# DorMouse.net
KiCad netlist of a schematic drawn in EAGLE
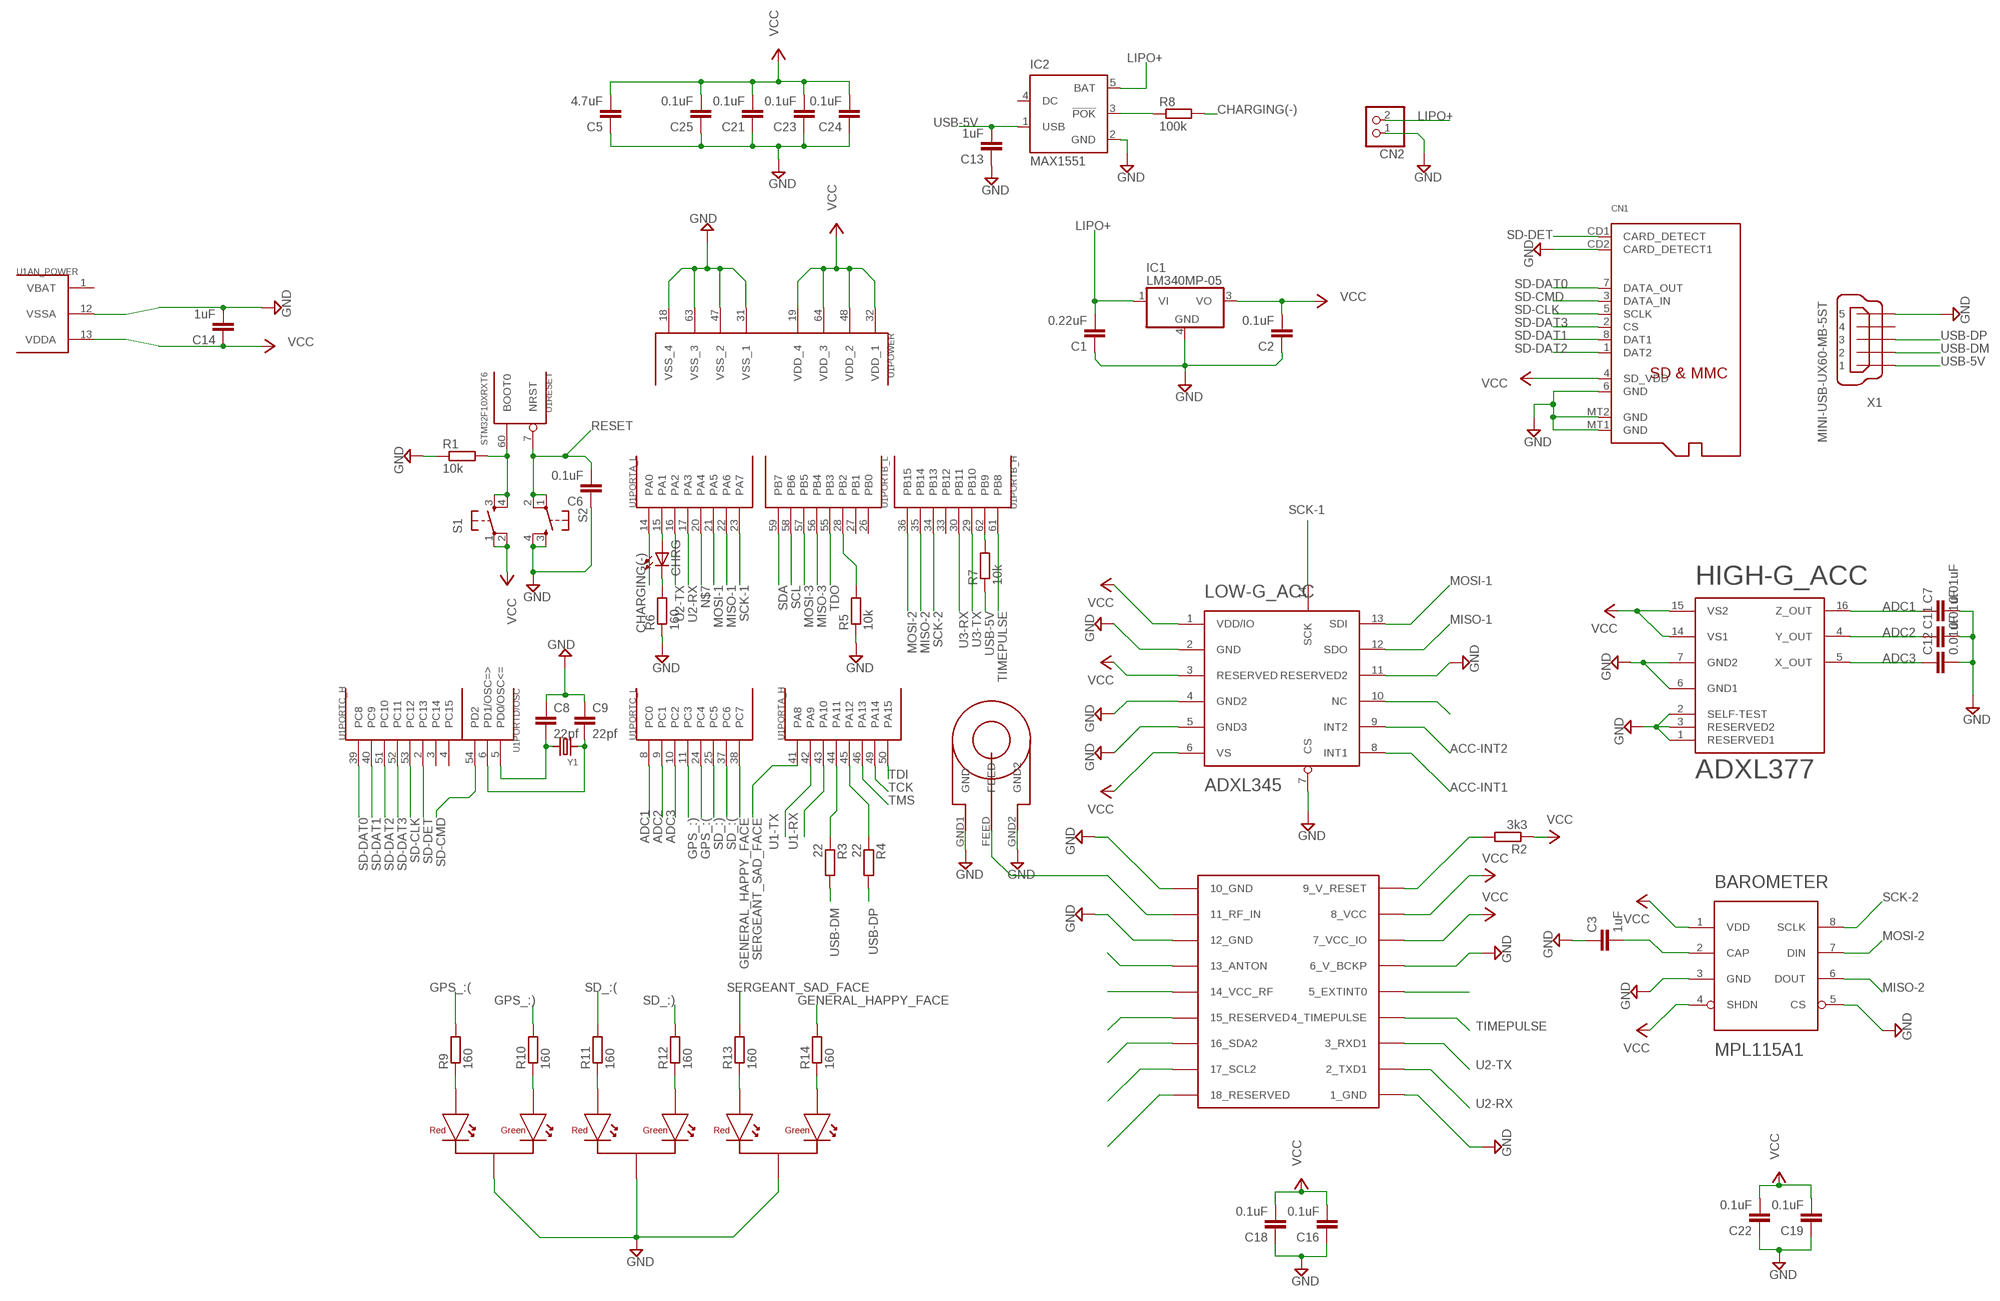
[diagram p0: schematic, sheet 1, part 1 of 2]
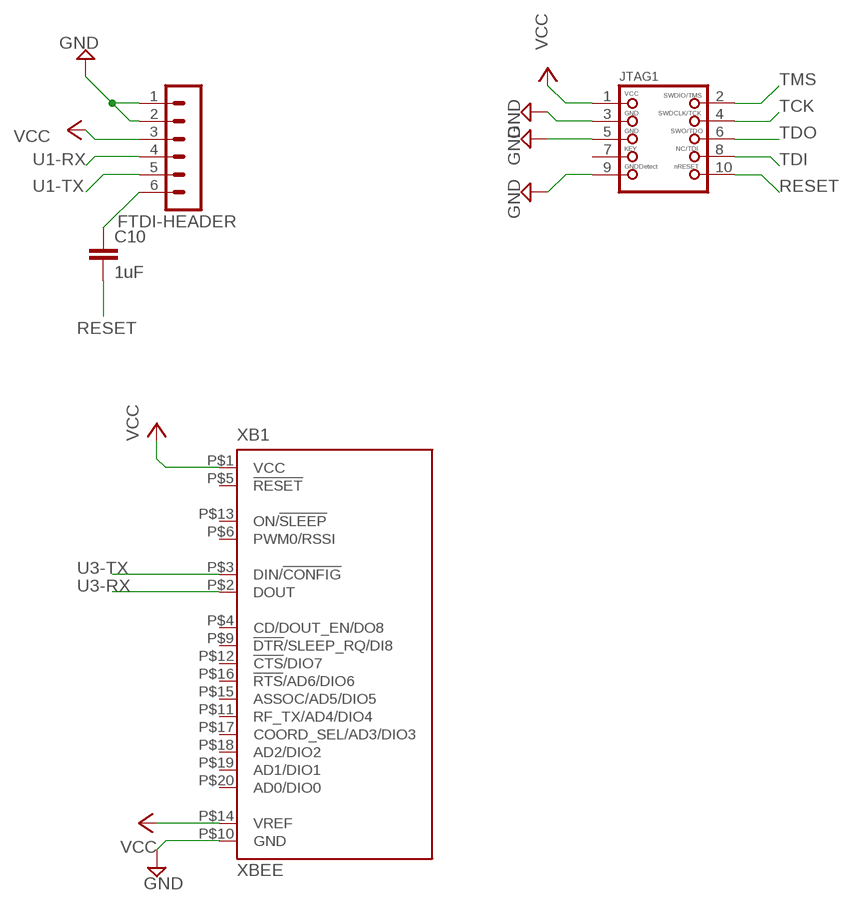
[diagram p1: schematic, sheet 1, part 2 of 2]

(export (version "E")
  (design (tool "Eeschema 10.0.6"))
  (components
    (comp (ref "BAROMETER")
      (value "MPL115A1")
      (footprint "eagle-import:LGA-8")
      (libsource (lib "eagle-import") (part "MPL115A1"))
    )
    (comp (ref "C1")
      (value "0.22uF")
      (footprint "eagle-import:C0402")
      (libsource (lib "eagle-import") (part "C-EUC0402"))
    )
    (comp (ref "C2")
      (value "0.1uF")
      (footprint "eagle-import:C0402")
      (libsource (lib "eagle-import") (part "C-EUC0402"))
    )
    (comp (ref "C3")
      (value "1uF")
      (footprint "eagle-import:C0402")
      (libsource (lib "eagle-import") (part "C-EUC0402"))
    )
    (comp (ref "C5")
      (value "4.7uF")
      (footprint "eagle-import:C0402")
      (libsource (lib "eagle-import") (part "C-EUC0402"))
    )
    (comp (ref "C6")
      (value "0.1uF")
      (footprint "eagle-import:C0402")
      (libsource (lib "eagle-import") (part "C-EUC0402"))
    )
    (comp (ref "C7")
      (value "0.01uF")
      (footprint "eagle-import:C0402")
      (libsource (lib "eagle-import") (part "C-EUC0402"))
    )
    (comp (ref "C8")
      (value "22pf")
      (footprint "eagle-import:C0402")
      (libsource (lib "eagle-import") (part "C-EUC0402"))
    )
    (comp (ref "C9")
      (value "22pf")
      (footprint "eagle-import:C0402")
      (libsource (lib "eagle-import") (part "C-EUC0402"))
    )
    (comp (ref "C10")
      (value "1uF")
      (footprint "eagle-import:C0402")
      (libsource (lib "eagle-import") (part "C-EUC0402"))
    )
    (comp (ref "C11")
      (value "0.01uF")
      (footprint "eagle-import:C0402")
      (libsource (lib "eagle-import") (part "C-EUC0402"))
    )
    (comp (ref "C12")
      (value "0.01uF")
      (footprint "eagle-import:C0402")
      (libsource (lib "eagle-import") (part "C-EUC0402"))
    )
    (comp (ref "C13")
      (value "1uF")
      (footprint "eagle-import:C0402")
      (libsource (lib "eagle-import") (part "C-EUC0402"))
    )
    (comp (ref "C14")
      (value "1uF")
      (footprint "eagle-import:C0402")
      (libsource (lib "eagle-import") (part "C-EUC0402"))
    )
    (comp (ref "C16")
      (value "0.1uF")
      (footprint "eagle-import:C0402")
      (libsource (lib "eagle-import") (part "C-EUC0402"))
    )
    (comp (ref "C18")
      (value "0.1uF")
      (footprint "eagle-import:C0402")
      (libsource (lib "eagle-import") (part "C-EUC0402"))
    )
    (comp (ref "C19")
      (value "0.1uF")
      (footprint "eagle-import:C0402")
      (libsource (lib "eagle-import") (part "C-EUC0402"))
    )
    (comp (ref "C21")
      (value "0.1uF")
      (footprint "eagle-import:C0402")
      (libsource (lib "eagle-import") (part "C-EUC0402"))
    )
    (comp (ref "C22")
      (value "0.1uF")
      (footprint "eagle-import:C0402")
      (libsource (lib "eagle-import") (part "C-EUC0402"))
    )
    (comp (ref "C23")
      (value "0.1uF")
      (footprint "eagle-import:C0402")
      (libsource (lib "eagle-import") (part "C-EUC0402"))
    )
    (comp (ref "C24")
      (value "0.1uF")
      (footprint "eagle-import:C0402")
      (libsource (lib "eagle-import") (part "C-EUC0402"))
    )
    (comp (ref "C25")
      (value "0.1uF")
      (footprint "eagle-import:C0402")
      (libsource (lib "eagle-import") (part "C-EUC0402"))
    )
    (comp (ref "CHRG")
      (value "LEDCHIPLED_0603")
      (footprint "eagle-import:CHIPLED_0603")
      (libsource (lib "eagle-import") (part "LEDCHIPLED_0603"))
    )
    (comp (ref "CN1")
      (value "MICROSD")
      (footprint "eagle-import:MICROSD")
      (libsource (lib "eagle-import") (part "MICROSD"))
    )
    (comp (ref "CN2")
      (value "JST_2PINSH2")
      (footprint "eagle-import:JSTSH2")
      (libsource (lib "eagle-import") (part "JST_2PINSH2"))
    )
    (comp (ref "FTDI-HEADER")
      (value "MA06-1")
      (footprint "eagle-import:MA06-1")
      (libsource (lib "eagle-import") (part "MA06-1"))
    )
    (comp (ref "GENERAL")
      (value "RED-GREEN_LED")
      (footprint "eagle-import:SOT23")
      (libsource (lib "eagle-import") (part "RED-GREEN_LED"))
    )
    (comp (ref "GPS")
      (value "UBLOX_MAX-6")
      (footprint "eagle-import:UBLOX_MAX-6")
      (libsource (lib "eagle-import") (part "UBLOX_MAX-6"))
    )
    (comp (ref "GPS-LED")
      (value "RED-GREEN_LED")
      (footprint "eagle-import:SOT23")
      (libsource (lib "eagle-import") (part "RED-GREEN_LED"))
    )
    (comp (ref "HIGH-G_ACC")
      (value "ADXL377")
      (footprint "eagle-import:LFCSP-16")
      (libsource (lib "eagle-import") (part "ADXL377"))
    )
    (comp (ref "IC1")
      (value "LM340MP-05")
      (footprint "eagle-import:SOT223")
      (libsource (lib "eagle-import") (part "LM340?-MP05"))
    )
    (comp (ref "IC2")
      (value "MAX1551")
      (footprint "eagle-import:SOT23-5L")
      (fields (field (name "MF") "MAXIM") (field (name "MPN") "MAX1551EZK-T"))
      (libsource (lib "eagle-import") (part "MAX1551"))
    )
    (comp (ref "JTAG1")
      (value "JTAG-CORTEXM3")
      (footprint "eagle-import:2X05_1.27MM_SMT")
      (libsource (lib "eagle-import") (part "JTAG-CORTEXM3"))
    )
    (comp (ref "LOW-G_ACC")
      (value "ADXL345")
      (footprint "eagle-import:LGA-14")
      (libsource (lib "eagle-import") (part "ADXL345"))
    )
    (comp (ref "R1")
      (value "10k")
      (footprint "eagle-import:R0402")
      (libsource (lib "eagle-import") (part "R-EU_R0402"))
    )
    (comp (ref "R2")
      (value "3k3")
      (footprint "eagle-import:R0402")
      (libsource (lib "eagle-import") (part "R-EU_R0402"))
    )
    (comp (ref "R3")
      (value "22")
      (footprint "eagle-import:R0402")
      (libsource (lib "eagle-import") (part "R-EU_R0402"))
    )
    (comp (ref "R4")
      (value "22")
      (footprint "eagle-import:R0402")
      (libsource (lib "eagle-import") (part "R-EU_R0402"))
    )
    (comp (ref "R5")
      (value "10k")
      (footprint "eagle-import:R0402")
      (libsource (lib "eagle-import") (part "R-EU_R0402"))
    )
    (comp (ref "R6")
      (value "160")
      (footprint "eagle-import:R0402")
      (libsource (lib "eagle-import") (part "R-EU_R0402"))
    )
    (comp (ref "R7")
      (value "10k")
      (footprint "eagle-import:R0402")
      (libsource (lib "eagle-import") (part "R-EU_R0402"))
    )
    (comp (ref "R8")
      (value "100k")
      (footprint "eagle-import:R0402")
      (libsource (lib "eagle-import") (part "R-EU_R0402"))
    )
    (comp (ref "R9")
      (value "160")
      (footprint "eagle-import:R0402")
      (libsource (lib "eagle-import") (part "R-EU_R0402"))
    )
    (comp (ref "R10")
      (value "160")
      (footprint "eagle-import:R0402")
      (libsource (lib "eagle-import") (part "R-EU_R0402"))
    )
    (comp (ref "R11")
      (value "160")
      (footprint "eagle-import:R0402")
      (libsource (lib "eagle-import") (part "R-EU_R0402"))
    )
    (comp (ref "R12")
      (value "160")
      (footprint "eagle-import:R0402")
      (libsource (lib "eagle-import") (part "R-EU_R0402"))
    )
    (comp (ref "R13")
      (value "160")
      (footprint "eagle-import:R0402")
      (libsource (lib "eagle-import") (part "R-EU_R0402"))
    )
    (comp (ref "R14")
      (value "160")
      (footprint "eagle-import:R0402")
      (libsource (lib "eagle-import") (part "R-EU_R0402"))
    )
    (comp (ref "S1")
      (value "TAC_SWITCHSMD")
      (footprint "eagle-import:TACTILE_SWITCH_SMD")
      (libsource (lib "eagle-import") (part "TAC_SWITCHSMD"))
    )
    (comp (ref "S2")
      (value "TAC_SWITCHSMD")
      (footprint "eagle-import:TACTILE_SWITCH_SMD")
      (libsource (lib "eagle-import") (part "TAC_SWITCHSMD"))
    )
    (comp (ref "SD-LED")
      (value "RED-GREEN_LED")
      (footprint "eagle-import:SOT23")
      (libsource (lib "eagle-import") (part "RED-GREEN_LED"))
    )
    (comp (ref "U$1")
      (value "SARANTEL-SR1202")
      (footprint "eagle-import:SARANTEL-SR1202")
      (libsource (lib "eagle-import") (part "SARANTEL-SR1202"))
    )
    (comp (ref "U1")
      (value "STM32F10XRXT6")
      (footprint "eagle-import:TQFP64")
      (libsource (lib "eagle-import") (part "STM32F10XRXT6"))
    )
    (comp (ref "X1")
      (value "MINI-USB-UX60-MB-5ST")
      (footprint "eagle-import:UX60-MB-5ST")
      (libsource (lib "eagle-import") (part "MINI-USB-UX60-MB-5ST"))
    )
    (comp (ref "XB1")
      (value "XBEE")
      (footprint "eagle-import:XBEE")
      (fields (field (name "MPN") "XBP24-Z7UIT-004"))
      (libsource (lib "eagle-import") (part "XBEE"))
    )
    (comp (ref "Y1")
      (value "CRYSTALSMD")
      (footprint "eagle-import:HC49UP")
      (libsource (lib "eagle-import") (part "CRYSTALSMD"))
    )
  )
  (nets
    (net (code "1") (name "/ACC-INT1") (class "Default")
      (node (ref "LOW-G_ACC") (pin "8") (pinfunction "INT1_8") (pintype "bidirectional"))
    )
    (net (code "2") (name "/ACC-INT2") (class "Default")
      (node (ref "LOW-G_ACC") (pin "9") (pinfunction "INT2_9") (pintype "bidirectional"))
    )
    (net (code "3") (name "/ADC1") (class "Default")
      (node (ref "C7") (pin "1") (pinfunction "1_1") (pintype "passive"))
      (node (ref "HIGH-G_ACC") (pin "16") (pinfunction "Z_OUT_16") (pintype "bidirectional"))
      (node (ref "U1") (pin "8") (pinfunction "PC0_8") (pintype "bidirectional"))
    )
    (net (code "4") (name "/ADC2") (class "Default")
      (node (ref "C11") (pin "1") (pinfunction "1_1") (pintype "passive"))
      (node (ref "HIGH-G_ACC") (pin "4") (pinfunction "Y_OUT_4") (pintype "bidirectional"))
      (node (ref "U1") (pin "9") (pinfunction "PC1_9") (pintype "bidirectional"))
    )
    (net (code "5") (name "/ADC3") (class "Default")
      (node (ref "C12") (pin "1") (pinfunction "1_1") (pintype "passive"))
      (node (ref "HIGH-G_ACC") (pin "5") (pinfunction "X_OUT_5") (pintype "bidirectional"))
      (node (ref "U1") (pin "10") (pinfunction "PC2_10") (pintype "bidirectional"))
    )
    (net (code "6") (name "/CHARGING(-)") (class "Default")
      (node (ref "R8") (pin "2") (pinfunction "2_2") (pintype "passive"))
      (node (ref "U1") (pin "14") (pinfunction "PA0_14") (pintype "bidirectional"))
    )
    (net (code "7") (name "/GENERAL_HAPPY_FACE") (class "Default")
      (node (ref "R14") (pin "2") (pinfunction "2_2") (pintype "passive"))
      (node (ref "U1") (pin "38") (pinfunction "PC7_38") (pintype "bidirectional"))
    )
    (net (code "8") (name "/GPS_:(") (class "Default")
      (node (ref "R9") (pin "2") (pinfunction "2_2") (pintype "passive"))
      (node (ref "U1") (pin "24") (pinfunction "PC4_24") (pintype "bidirectional"))
    )
    (net (code "9") (name "/GPS_:)") (class "Default")
      (node (ref "R10") (pin "2") (pinfunction "2_2") (pintype "passive"))
      (node (ref "U1") (pin "11") (pinfunction "PC3_11") (pintype "bidirectional"))
    )
    (net (code "10") (name "/LIPO+") (class "Default")
      (node (ref "C1") (pin "2") (pinfunction "2_2") (pintype "passive"))
      (node (ref "CN2") (pin "2") (pinfunction "2_2") (pintype "passive"))
      (node (ref "IC1") (pin "1") (pinfunction "VI_1") (pintype "input"))
      (node (ref "IC2") (pin "5") (pinfunction "BAT_5") (pintype "passive"))
    )
    (net (code "11") (name "/MISO-1") (class "Default")
      (node (ref "LOW-G_ACC") (pin "12") (pinfunction "SDO_12") (pintype "bidirectional"))
      (node (ref "U1") (pin "22") (pinfunction "PA6_22") (pintype "bidirectional"))
    )
    (net (code "12") (name "/MISO-2") (class "Default")
      (node (ref "BAROMETER") (pin "6") (pinfunction "DOUT_6") (pintype "bidirectional"))
      (node (ref "U1") (pin "35") (pinfunction "PB14_35") (pintype "bidirectional"))
    )
    (net (code "13") (name "/MISO-3") (class "Default")
      (node (ref "U1") (pin "56") (pinfunction "PB4_56") (pintype "bidirectional"))
    )
    (net (code "14") (name "/MOSI-1") (class "Default")
      (node (ref "LOW-G_ACC") (pin "13") (pinfunction "SDI_13") (pintype "bidirectional"))
      (node (ref "U1") (pin "21") (pinfunction "PA5_21") (pintype "bidirectional"))
    )
    (net (code "15") (name "/MOSI-2") (class "Default")
      (node (ref "BAROMETER") (pin "7") (pinfunction "DIN_7") (pintype "bidirectional"))
      (node (ref "U1") (pin "36") (pinfunction "PB15_36") (pintype "bidirectional"))
    )
    (net (code "16") (name "/MOSI-3") (class "Default")
      (node (ref "U1") (pin "57") (pinfunction "PB5_57") (pintype "bidirectional"))
    )
    (net (code "17") (name "/N$7") (class "Default")
      (node (ref "U1") (pin "20") (pinfunction "PA4_20") (pintype "bidirectional"))
    )
    (net (code "18") (name "/RESET") (class "Default")
      (node (ref "C10") (pin "2") (pinfunction "2_2") (pintype "passive"))
      (node (ref "C6") (pin "2") (pinfunction "2_2") (pintype "passive"))
      (node (ref "JTAG1") (pin "10") (pinfunction "10_10") (pintype "passive"))
      (node (ref "S2") (pin "1") (pinfunction "1_1") (pintype "passive"))
      (node (ref "S2") (pin "2") (pinfunction "2_2") (pintype "passive"))
      (node (ref "U1") (pin "7") (pinfunction "NRST_7") (pintype "input"))
    )
    (net (code "19") (name "/SCK-1") (class "Default")
      (node (ref "LOW-G_ACC") (pin "14") (pinfunction "SCK_14") (pintype "bidirectional"))
      (node (ref "U1") (pin "23") (pinfunction "PA7_23") (pintype "bidirectional"))
    )
    (net (code "20") (name "/SCK-2") (class "Default")
      (node (ref "BAROMETER") (pin "8") (pinfunction "SCLK_8") (pintype "bidirectional"))
      (node (ref "U1") (pin "34") (pinfunction "PB13_34") (pintype "bidirectional"))
    )
    (net (code "21") (name "/SCL") (class "Default")
      (node (ref "U1") (pin "58") (pinfunction "PB6_58") (pintype "bidirectional"))
    )
    (net (code "22") (name "/SD-CLK") (class "Default")
      (node (ref "CN1") (pin "5") (pinfunction "SCLK_5") (pintype "input"))
      (node (ref "U1") (pin "53") (pinfunction "PC12_53") (pintype "bidirectional"))
    )
    (net (code "23") (name "/SD-CMD") (class "Default")
      (node (ref "CN1") (pin "3") (pinfunction "DATA_IN_3") (pintype "input"))
      (node (ref "U1") (pin "54") (pinfunction "PD2_54") (pintype "bidirectional"))
    )
    (net (code "24") (name "/SD-DAT0") (class "Default")
      (node (ref "CN1") (pin "7") (pinfunction "DATA_OUT_7") (pintype "output"))
      (node (ref "U1") (pin "39") (pinfunction "PC8_39") (pintype "bidirectional"))
    )
    (net (code "25") (name "/SD-DAT1") (class "Default")
      (node (ref "CN1") (pin "8") (pinfunction "DAT1_8") (pintype "bidirectional"))
      (node (ref "U1") (pin "40") (pinfunction "PC9_40") (pintype "bidirectional"))
    )
    (net (code "26") (name "/SD-DAT2") (class "Default")
      (node (ref "CN1") (pin "1") (pinfunction "DAT2_1") (pintype "bidirectional"))
      (node (ref "U1") (pin "51") (pinfunction "PC10_51") (pintype "bidirectional"))
    )
    (net (code "27") (name "/SD-DAT3") (class "Default")
      (node (ref "CN1") (pin "2") (pinfunction "CS_2") (pintype "input"))
      (node (ref "U1") (pin "52") (pinfunction "PC11_52") (pintype "bidirectional"))
    )
    (net (code "28") (name "/SD-DET") (class "Default")
      (node (ref "CN1") (pin "CD1") (pinfunction "CARD_DETECT_CD1") (pintype "passive"))
      (node (ref "U1") (pin "2") (pinfunction "PC13_2") (pintype "bidirectional"))
    )
    (net (code "29") (name "/SDA") (class "Default")
      (node (ref "U1") (pin "59") (pinfunction "PB7_59") (pintype "bidirectional"))
    )
    (net (code "30") (name "/SD_:(") (class "Default")
      (node (ref "R11") (pin "2") (pinfunction "2_2") (pintype "passive"))
      (node (ref "U1") (pin "37") (pinfunction "PC6_37") (pintype "bidirectional"))
    )
    (net (code "31") (name "/SD_:)") (class "Default")
      (node (ref "R12") (pin "2") (pinfunction "2_2") (pintype "passive"))
      (node (ref "U1") (pin "25") (pinfunction "PC5_25") (pintype "bidirectional"))
    )
    (net (code "32") (name "/SERGEANT_SAD_FACE") (class "Default")
      (node (ref "R13") (pin "2") (pinfunction "2_2") (pintype "passive"))
      (node (ref "U1") (pin "41") (pinfunction "PA8_41") (pintype "bidirectional"))
    )
    (net (code "33") (name "/TCK") (class "Default")
      (node (ref "JTAG1") (pin "4") (pinfunction "4_4") (pintype "passive"))
      (node (ref "U1") (pin "49") (pinfunction "PA14_49") (pintype "bidirectional"))
    )
    (net (code "34") (name "/TDI") (class "Default")
      (node (ref "JTAG1") (pin "8") (pinfunction "8_8") (pintype "passive"))
      (node (ref "U1") (pin "50") (pinfunction "PA15_50") (pintype "bidirectional"))
    )
    (net (code "35") (name "/TDO") (class "Default")
      (node (ref "JTAG1") (pin "6") (pinfunction "6_6") (pintype "passive"))
      (node (ref "U1") (pin "55") (pinfunction "PB3_55") (pintype "bidirectional"))
    )
    (net (code "36") (name "/TIMEPULSE") (class "Default")
      (node (ref "GPS") (pin "4_TIMEPULSE") (pinfunction "4_TIMEPULSE_4_TIMEPULSE") (pintype "bidirectional"))
      (node (ref "U1") (pin "61") (pinfunction "PB8_61") (pintype "bidirectional"))
    )
    (net (code "37") (name "/TMS") (class "Default")
      (node (ref "JTAG1") (pin "2") (pinfunction "2_2") (pintype "passive"))
      (node (ref "U1") (pin "46") (pinfunction "PA13_46") (pintype "bidirectional"))
    )
    (net (code "38") (name "/U1-RX") (class "Default")
      (node (ref "FTDI-HEADER") (pin "4") (pinfunction "4_4") (pintype "passive"))
      (node (ref "U1") (pin "43") (pinfunction "PA10_43") (pintype "bidirectional"))
    )
    (net (code "39") (name "/U1-TX") (class "Default")
      (node (ref "FTDI-HEADER") (pin "5") (pinfunction "5_5") (pintype "passive"))
      (node (ref "U1") (pin "42") (pinfunction "PA9_42") (pintype "bidirectional"))
    )
    (net (code "40") (name "/U2-RX") (class "Default")
      (node (ref "GPS") (pin "2_TXD1") (pinfunction "2_TXD1_2_TXD1") (pintype "bidirectional"))
      (node (ref "U1") (pin "17") (pinfunction "PA3_17") (pintype "bidirectional"))
    )
    (net (code "41") (name "/U2-TX") (class "Default")
      (node (ref "GPS") (pin "3_RXD1") (pinfunction "3_RXD1_3_RXD1") (pintype "bidirectional"))
      (node (ref "U1") (pin "16") (pinfunction "PA2_16") (pintype "bidirectional"))
    )
    (net (code "42") (name "/U3-RX") (class "Default")
      (node (ref "U1") (pin "30") (pinfunction "PB11_30") (pintype "bidirectional"))
      (node (ref "XB1") (pin "P$2") (pinfunction "DOUT_P$2") (pintype "output"))
    )
    (net (code "43") (name "/U3-TX") (class "Default")
      (node (ref "U1") (pin "29") (pinfunction "PB10_29") (pintype "bidirectional"))
      (node (ref "XB1") (pin "P$3") (pinfunction "DIN/~{CONFIG}_P$3") (pintype "input"))
    )
    (net (code "44") (name "/USB-5V") (class "Default")
      (node (ref "C13") (pin "2") (pinfunction "2_2") (pintype "passive"))
      (node (ref "IC2") (pin "1") (pinfunction "USB_1") (pintype "input"))
      (node (ref "R7") (pin "1") (pinfunction "1_1") (pintype "passive"))
      (node (ref "X1") (pin "1") (pinfunction "1_1") (pintype "input"))
    )
    (net (code "45") (name "/USB-DM") (class "Default")
      (node (ref "R3") (pin "2") (pinfunction "2_2") (pintype "passive"))
      (node (ref "X1") (pin "2") (pinfunction "2_2") (pintype "input"))
    )
    (net (code "46") (name "/USB-DP") (class "Default")
      (node (ref "R4") (pin "2") (pinfunction "2_2") (pintype "passive"))
      (node (ref "X1") (pin "3") (pinfunction "3_3") (pintype "input"))
    )
    (net (code "47") (name "/VBAT") (class "Default")
      (node (ref "U1") (pin "1") (pinfunction "VBAT_1") (pintype "power_in"))
    )
    (net (code "48") (name "GND") (class "Default")
      (node (ref "BAROMETER") (pin "3") (pinfunction "GND_3") (pintype "bidirectional"))
      (node (ref "BAROMETER") (pin "5") (pinfunction "CS_5") (pintype "bidirectional"))
      (node (ref "C1") (pin "1") (pinfunction "1_1") (pintype "passive"))
      (node (ref "C11") (pin "2") (pinfunction "2_2") (pintype "passive"))
      (node (ref "C12") (pin "2") (pinfunction "2_2") (pintype "passive"))
      (node (ref "C13") (pin "1") (pinfunction "1_1") (pintype "passive"))
      (node (ref "C14") (pin "2") (pinfunction "2_2") (pintype "passive"))
      (node (ref "C16") (pin "1") (pinfunction "1_1") (pintype "passive"))
      (node (ref "C18") (pin "1") (pinfunction "1_1") (pintype "passive"))
      (node (ref "C19") (pin "1") (pinfunction "1_1") (pintype "passive"))
      (node (ref "C2") (pin "1") (pinfunction "1_1") (pintype "passive"))
      (node (ref "C21") (pin "1") (pinfunction "1_1") (pintype "passive"))
      (node (ref "C22") (pin "1") (pinfunction "1_1") (pintype "passive"))
      (node (ref "C23") (pin "1") (pinfunction "1_1") (pintype "passive"))
      (node (ref "C24") (pin "1") (pinfunction "1_1") (pintype "passive"))
      (node (ref "C25") (pin "1") (pinfunction "1_1") (pintype "passive"))
      (node (ref "C3") (pin "1") (pinfunction "1_1") (pintype "passive"))
      (node (ref "C5") (pin "1") (pinfunction "1_1") (pintype "passive"))
      (node (ref "C6") (pin "1") (pinfunction "1_1") (pintype "passive"))
      (node (ref "C7") (pin "2") (pinfunction "2_2") (pintype "passive"))
      (node (ref "C8") (pin "1") (pinfunction "1_1") (pintype "passive"))
      (node (ref "C9") (pin "1") (pinfunction "1_1") (pintype "passive"))
      (node (ref "CN1") (pin "6") (pinfunction "GND_6") (pintype "power_in"))
      (node (ref "CN1") (pin "CD2") (pinfunction "CARD_DETECT1_CD2") (pintype "passive"))
      (node (ref "CN1") (pin "MT1") (pinfunction "GND_MT1") (pintype "power_in"))
      (node (ref "CN1") (pin "MT2") (pinfunction "GND_MT2") (pintype "power_in"))
      (node (ref "CN2") (pin "1") (pinfunction "1_1") (pintype "passive"))
      (node (ref "FTDI-HEADER") (pin "1") (pinfunction "1_1") (pintype "passive"))
      (node (ref "FTDI-HEADER") (pin "2") (pinfunction "2_2") (pintype "passive"))
      (node (ref "GENERAL") (pin "3") (pinfunction "CATHODE_3") (pintype "bidirectional"))
      (node (ref "GPS") (pin "10_GND") (pinfunction "10_GND_10_GND") (pintype "power_in"))
      (node (ref "GPS") (pin "12_GND") (pinfunction "12_GND_12_GND") (pintype "power_in"))
      (node (ref "GPS") (pin "1_GND") (pinfunction "1_GND_1_GND") (pintype "power_in"))
      (node (ref "GPS") (pin "6_V_BCKP") (pinfunction "6_V_BCKP_6_V_BCKP") (pintype "bidirectional"))
      (node (ref "GPS-LED") (pin "3") (pinfunction "CATHODE_3") (pintype "bidirectional"))
      (node (ref "HIGH-G_ACC") (pin "1") (pinfunction "RESERVED1_1") (pintype "bidirectional"))
      (node (ref "HIGH-G_ACC") (pin "2") (pinfunction "SELF-TEST_2") (pintype "bidirectional"))
      (node (ref "HIGH-G_ACC") (pin "3") (pinfunction "RESERVED2_3") (pintype "bidirectional"))
      (node (ref "HIGH-G_ACC") (pin "6") (pinfunction "GND1_6") (pintype "bidirectional"))
      (node (ref "HIGH-G_ACC") (pin "7") (pinfunction "GND2_7") (pintype "bidirectional"))
      (node (ref "IC1") (pin "4") (pinfunction "GND_4") (pintype "passive"))
      (node (ref "IC2") (pin "2") (pinfunction "GND_2") (pintype "power_in"))
      (node (ref "JTAG1") (pin "3") (pinfunction "3_3") (pintype "passive"))
      (node (ref "JTAG1") (pin "5") (pinfunction "5_5") (pintype "passive"))
      (node (ref "JTAG1") (pin "9") (pinfunction "9_9") (pintype "passive"))
      (node (ref "LOW-G_ACC") (pin "11") (pinfunction "RESERVED2_11") (pintype "bidirectional"))
      (node (ref "LOW-G_ACC") (pin "2") (pinfunction "GND_2") (pintype "bidirectional"))
      (node (ref "LOW-G_ACC") (pin "4") (pinfunction "GND2_4") (pintype "bidirectional"))
      (node (ref "LOW-G_ACC") (pin "5") (pinfunction "GND3_5") (pintype "bidirectional"))
      (node (ref "LOW-G_ACC") (pin "7") (pinfunction "CS_7") (pintype "bidirectional"))
      (node (ref "R1") (pin "1") (pinfunction "1_1") (pintype "passive"))
      (node (ref "R5") (pin "1") (pinfunction "1_1") (pintype "passive"))
      (node (ref "R6") (pin "1") (pinfunction "1_1") (pintype "passive"))
      (node (ref "S2") (pin "3") (pinfunction "3_3") (pintype "passive"))
      (node (ref "S2") (pin "4") (pinfunction "4_4") (pintype "passive"))
      (node (ref "SD-LED") (pin "3") (pinfunction "CATHODE_3") (pintype "bidirectional"))
      (node (ref "U$1") (pin "GND1") (pinfunction "GND_GND1") (pintype "bidirectional"))
      (node (ref "U$1") (pin "GND2") (pinfunction "GND2_GND2") (pintype "bidirectional"))
      (node (ref "U1") (pin "12") (pinfunction "VSSA_12") (pintype "power_in"))
      (node (ref "U1") (pin "18") (pinfunction "VSS_4_18") (pintype "power_in"))
      (node (ref "U1") (pin "31") (pinfunction "VSS_1_31") (pintype "power_in"))
      (node (ref "U1") (pin "47") (pinfunction "VSS_2_47") (pintype "power_in"))
      (node (ref "U1") (pin "63") (pinfunction "VSS_3_63") (pintype "power_in"))
      (node (ref "X1") (pin "5") (pinfunction "5_5") (pintype "input"))
      (node (ref "XB1") (pin "P$10") (pinfunction "GND_P$10") (pintype "power_in"))
    )
    (net (code "49") (name "Net-(BAROMETER-CAP)") (class "Default")
      (node (ref "BAROMETER") (pin "2") (pinfunction "CAP_2") (pintype "bidirectional"))
      (node (ref "C3") (pin "2") (pinfunction "2_2") (pintype "passive"))
    )
    (net (code "50") (name "Net-(C10-Pad1)") (class "Default")
      (node (ref "C10") (pin "1") (pinfunction "1_1") (pintype "passive"))
      (node (ref "FTDI-HEADER") (pin "6") (pinfunction "6_6") (pintype "passive"))
    )
    (net (code "51") (name "Net-(CHRG-PadC)") (class "Default")
      (node (ref "CHRG") (pin "C") (pinfunction "C_C") (pintype "passive"))
      (node (ref "R6") (pin "2") (pinfunction "2_2") (pintype "passive"))
    )
    (net (code "52") (name "Net-(GENERAL-GREEN-ANODE)") (class "Default")
      (node (ref "GENERAL") (pin "2") (pinfunction "GREEN-ANODE_2") (pintype "bidirectional"))
      (node (ref "R14") (pin "1") (pinfunction "1_1") (pintype "passive"))
    )
    (net (code "53") (name "Net-(GENERAL-RED-ANODE)") (class "Default")
      (node (ref "GENERAL") (pin "1") (pinfunction "RED-ANODE_1") (pintype "bidirectional"))
      (node (ref "R13") (pin "1") (pinfunction "1_1") (pintype "passive"))
    )
    (net (code "54") (name "Net-(GPS-LED-GREEN-ANODE)") (class "Default")
      (node (ref "GPS-LED") (pin "2") (pinfunction "GREEN-ANODE_2") (pintype "bidirectional"))
      (node (ref "R10") (pin "1") (pinfunction "1_1") (pintype "passive"))
    )
    (net (code "55") (name "Net-(GPS-LED-RED-ANODE)") (class "Default")
      (node (ref "GPS-LED") (pin "1") (pinfunction "RED-ANODE_1") (pintype "bidirectional"))
      (node (ref "R9") (pin "1") (pinfunction "1_1") (pintype "passive"))
    )
    (net (code "56") (name "Net-(GPS-Pad9_V_RESET)") (class "Default")
      (node (ref "GPS") (pin "9_V_RESET") (pinfunction "9_V_RESET_9_V_RESET") (pintype "power_in"))
      (node (ref "R2") (pin "2") (pinfunction "2_2") (pintype "passive"))
    )
    (net (code "57") (name "Net-(GPS-Pad11_RF_IN)") (class "Default")
      (node (ref "GPS") (pin "11_RF_IN") (pinfunction "11_RF_IN_11_RF_IN") (pintype "bidirectional"))
      (node (ref "U$1") (pin "FEED") (pinfunction "FEED_FEED") (pintype "bidirectional"))
    )
    (net (code "58") (name "Net-(IC2-~{POK})") (class "Default")
      (node (ref "IC2") (pin "3") (pinfunction "~{POK}_3") (pintype "output"))
      (node (ref "R8") (pin "1") (pinfunction "1_1") (pintype "passive"))
    )
    (net (code "59") (name "Net-(SD-LED-GREEN-ANODE)") (class "Default")
      (node (ref "R12") (pin "1") (pinfunction "1_1") (pintype "passive"))
      (node (ref "SD-LED") (pin "2") (pinfunction "GREEN-ANODE_2") (pintype "bidirectional"))
    )
    (net (code "60") (name "Net-(SD-LED-RED-ANODE)") (class "Default")
      (node (ref "R11") (pin "1") (pinfunction "1_1") (pintype "passive"))
      (node (ref "SD-LED") (pin "1") (pinfunction "RED-ANODE_1") (pintype "bidirectional"))
    )
    (net (code "61") (name "Net-(U1B-PA11)") (class "Default")
      (node (ref "R3") (pin "1") (pinfunction "1_1") (pintype "passive"))
      (node (ref "U1") (pin "44") (pinfunction "PA11_44") (pintype "bidirectional"))
    )
    (net (code "62") (name "Net-(U1B-PA12)") (class "Default")
      (node (ref "R4") (pin "1") (pinfunction "1_1") (pintype "passive"))
      (node (ref "U1") (pin "45") (pinfunction "PA12_45") (pintype "bidirectional"))
    )
    (net (code "63") (name "Net-(U1C-PA1)") (class "Default")
      (node (ref "CHRG") (pin "A") (pinfunction "A_A") (pintype "passive"))
      (node (ref "U1") (pin "15") (pinfunction "PA1_15") (pintype "bidirectional"))
    )
    (net (code "64") (name "Net-(U1D-PB9)") (class "Default")
      (node (ref "R7") (pin "2") (pinfunction "2_2") (pintype "passive"))
      (node (ref "U1") (pin "62") (pinfunction "PB9_62") (pintype "bidirectional"))
    )
    (net (code "65") (name "Net-(U1E-PB2)") (class "Default")
      (node (ref "R5") (pin "2") (pinfunction "2_2") (pintype "passive"))
      (node (ref "U1") (pin "28") (pinfunction "PB2_28") (pintype "bidirectional"))
    )
    (net (code "66") (name "Net-(U1H-PD0{slash}OSC<=)") (class "Default")
      (node (ref "C8") (pin "2") (pinfunction "2_2") (pintype "passive"))
      (node (ref "U1") (pin "5") (pinfunction "PD0/OSC<=_5") (pintype "bidirectional"))
      (node (ref "Y1") (pin "2") (pinfunction "2_2") (pintype "passive"))
    )
    (net (code "67") (name "Net-(U1H-PD1{slash}OSC=>)") (class "Default")
      (node (ref "C9") (pin "2") (pinfunction "2_2") (pintype "passive"))
      (node (ref "U1") (pin "6") (pinfunction "PD1/OSC=>_6") (pintype "bidirectional"))
      (node (ref "Y1") (pin "1") (pinfunction "1_1") (pintype "passive"))
    )
    (net (code "68") (name "Net-(U1J-BOOT0)") (class "Default")
      (node (ref "R1") (pin "2") (pinfunction "2_2") (pintype "passive"))
      (node (ref "S1") (pin "3") (pinfunction "3_3") (pintype "passive"))
      (node (ref "S1") (pin "4") (pinfunction "4_4") (pintype "passive"))
      (node (ref "U1") (pin "60") (pinfunction "BOOT0_60") (pintype "input"))
    )
    (net (code "69") (name "VCC") (class "Default")
      (node (ref "BAROMETER") (pin "1") (pinfunction "VDD_1") (pintype "bidirectional"))
      (node (ref "BAROMETER") (pin "4") (pinfunction "SHDN_4") (pintype "bidirectional"))
      (node (ref "C14") (pin "1") (pinfunction "1_1") (pintype "passive"))
      (node (ref "C16") (pin "2") (pinfunction "2_2") (pintype "passive"))
      (node (ref "C18") (pin "2") (pinfunction "2_2") (pintype "passive"))
      (node (ref "C19") (pin "2") (pinfunction "2_2") (pintype "passive"))
      (node (ref "C2") (pin "2") (pinfunction "2_2") (pintype "passive"))
      (node (ref "C21") (pin "2") (pinfunction "2_2") (pintype "passive"))
      (node (ref "C22") (pin "2") (pinfunction "2_2") (pintype "passive"))
      (node (ref "C23") (pin "2") (pinfunction "2_2") (pintype "passive"))
      (node (ref "C24") (pin "2") (pinfunction "2_2") (pintype "passive"))
      (node (ref "C25") (pin "2") (pinfunction "2_2") (pintype "passive"))
      (node (ref "C5") (pin "2") (pinfunction "2_2") (pintype "passive"))
      (node (ref "CN1") (pin "4") (pinfunction "SD_VDD_4") (pintype "power_in"))
      (node (ref "FTDI-HEADER") (pin "3") (pinfunction "3_3") (pintype "passive"))
      (node (ref "GPS") (pin "7_VCC_IO") (pinfunction "7_VCC_IO_7_VCC_IO") (pintype "power_in"))
      (node (ref "GPS") (pin "8_VCC") (pinfunction "8_VCC_8_VCC") (pintype "power_in"))
      (node (ref "HIGH-G_ACC") (pin "14") (pinfunction "VS1_14") (pintype "bidirectional"))
      (node (ref "HIGH-G_ACC") (pin "15") (pinfunction "VS2_15") (pintype "bidirectional"))
      (node (ref "IC1") (pin "3") (pinfunction "VO_3") (pintype "passive"))
      (node (ref "JTAG1") (pin "1") (pinfunction "1_1") (pintype "passive"))
      (node (ref "LOW-G_ACC") (pin "1") (pinfunction "VDD/IO_1") (pintype "bidirectional"))
      (node (ref "LOW-G_ACC") (pin "3") (pinfunction "RESERVED_3") (pintype "bidirectional"))
      (node (ref "LOW-G_ACC") (pin "6") (pinfunction "VS_6") (pintype "bidirectional"))
      (node (ref "R2") (pin "1") (pinfunction "1_1") (pintype "passive"))
      (node (ref "S1") (pin "1") (pinfunction "1_1") (pintype "passive"))
      (node (ref "S1") (pin "2") (pinfunction "2_2") (pintype "passive"))
      (node (ref "U1") (pin "13") (pinfunction "VDDA_13") (pintype "power_in"))
      (node (ref "U1") (pin "19") (pinfunction "VDD_4_19") (pintype "power_in"))
      (node (ref "U1") (pin "32") (pinfunction "VDD_1_32") (pintype "power_in"))
      (node (ref "U1") (pin "48") (pinfunction "VDD_2_48") (pintype "power_in"))
      (node (ref "U1") (pin "64") (pinfunction "VDD_3_64") (pintype "power_in"))
      (node (ref "XB1") (pin "P$1") (pinfunction "VCC_P$1") (pintype "power_in"))
      (node (ref "XB1") (pin "P$14") (pinfunction "VREF_P$14") (pintype "input"))
    )
    (net (code "70") (name "unconnected-(GPS-Pad5_EXTINT0)") (class "Default")
      (node (ref "GPS") (pin "5_EXTINT0") (pinfunction "5_EXTINT0_5_EXTINT0") (pintype "bidirectional"))
    )
    (net (code "71") (name "unconnected-(GPS-Pad13_ANTON)") (class "Default")
      (node (ref "GPS") (pin "13_ANTON") (pinfunction "13_ANTON_13_ANTON") (pintype "bidirectional"))
    )
    (net (code "72") (name "unconnected-(GPS-Pad14_VCC_RF)") (class "Default")
      (node (ref "GPS") (pin "14_VCC_RF") (pinfunction "14_VCC_RF_14_VCC_RF") (pintype "bidirectional"))
    )
    (net (code "73") (name "unconnected-(GPS-Pad15_RESERVED)") (class "Default")
      (node (ref "GPS") (pin "15_RESERVED") (pinfunction "15_RESERVED_15_RESERVED") (pintype "bidirectional"))
    )
    (net (code "74") (name "unconnected-(GPS-Pad16_SDA2)") (class "Default")
      (node (ref "GPS") (pin "16_SDA2") (pinfunction "16_SDA2_16_SDA2") (pintype "bidirectional"))
    )
    (net (code "75") (name "unconnected-(GPS-Pad17_SCL2)") (class "Default")
      (node (ref "GPS") (pin "17_SCL2") (pinfunction "17_SCL2_17_SCL2") (pintype "bidirectional"))
    )
    (net (code "76") (name "unconnected-(GPS-Pad18_RESERVED)") (class "Default")
      (node (ref "GPS") (pin "18_RESERVED") (pinfunction "18_RESERVED_18_RESERVED") (pintype "bidirectional"))
    )
    (net (code "77") (name "unconnected-(IC2-DC-Pad4)") (class "Default")
      (node (ref "IC2") (pin "4") (pinfunction "DC_4") (pintype "input"))
    )
    (net (code "78") (name "unconnected-(JTAG1-Pad7)") (class "Default")
      (node (ref "JTAG1") (pin "7") (pinfunction "7_7") (pintype "passive"))
    )
    (net (code "79") (name "unconnected-(LOW-G_ACC-NC-Pad10)") (class "Default")
      (node (ref "LOW-G_ACC") (pin "10") (pinfunction "NC_10") (pintype "bidirectional"))
    )
    (net (code "80") (name "unconnected-(U1D-PB12-Pad33)") (class "Default")
      (node (ref "U1") (pin "33") (pinfunction "PB12_33") (pintype "bidirectional"))
    )
    (net (code "81") (name "unconnected-(U1E-PB0-Pad26)") (class "Default")
      (node (ref "U1") (pin "26") (pinfunction "PB0_26") (pintype "bidirectional"))
    )
    (net (code "82") (name "unconnected-(U1E-PB1-Pad27)") (class "Default")
      (node (ref "U1") (pin "27") (pinfunction "PB1_27") (pintype "bidirectional"))
    )
    (net (code "83") (name "unconnected-(U1F-PC14-Pad3)") (class "Default")
      (node (ref "U1") (pin "3") (pinfunction "PC14_3") (pintype "bidirectional"))
    )
    (net (code "84") (name "unconnected-(U1F-PC15-Pad4)") (class "Default")
      (node (ref "U1") (pin "4") (pinfunction "PC15_4") (pintype "bidirectional"))
    )
    (net (code "85") (name "unconnected-(X1-Pad4)") (class "Default")
      (node (ref "X1") (pin "4") (pinfunction "4_4") (pintype "input"))
    )
    (net (code "86") (name "unconnected-(XB1-AD0{slash}DIO0-PadP$20)") (class "Default")
      (node (ref "XB1") (pin "P$20") (pinfunction "AD0/DIO0_P$20") (pintype "bidirectional"))
    )
    (net (code "87") (name "unconnected-(XB1-AD1{slash}DIO1-PadP$19)") (class "Default")
      (node (ref "XB1") (pin "P$19") (pinfunction "AD1/DIO1_P$19") (pintype "bidirectional"))
    )
    (net (code "88") (name "unconnected-(XB1-AD2{slash}DIO2-PadP$18)") (class "Default")
      (node (ref "XB1") (pin "P$18") (pinfunction "AD2/DIO2_P$18") (pintype "bidirectional"))
    )
    (net (code "89") (name "unconnected-(XB1-ASSOC{slash}AD5{slash}DIO5-PadP$15)") (class "Default")
      (node (ref "XB1") (pin "P$15") (pinfunction "ASSOC/AD5/DIO5_P$15") (pintype "bidirectional"))
    )
    (net (code "90") (name "unconnected-(XB1-CD{slash}DOUT_EN{slash}DO8-PadP$4)") (class "Default")
      (node (ref "XB1") (pin "P$4") (pinfunction "CD/DOUT_EN/DO8_P$4") (pintype "output"))
    )
    (net (code "91") (name "unconnected-(XB1-COORD_SEL{slash}AD3{slash}DIO3-PadP$17)") (class "Default")
      (node (ref "XB1") (pin "P$17") (pinfunction "COORD_SEL/AD3/DIO3_P$17") (pintype "bidirectional"))
    )
    (net (code "92") (name "unconnected-(XB1-ON{slash}~{SLEEP}-PadP$13)") (class "Default")
      (node (ref "XB1") (pin "P$13") (pinfunction "ON/~{SLEEP}_P$13") (pintype "output"))
    )
    (net (code "93") (name "unconnected-(XB1-PWM0{slash}RSSI-PadP$6)") (class "Default")
      (node (ref "XB1") (pin "P$6") (pinfunction "PWM0/RSSI_P$6") (pintype "output"))
    )
    (net (code "94") (name "unconnected-(XB1-RF_TX{slash}AD4{slash}DIO4-PadP$11)") (class "Default")
      (node (ref "XB1") (pin "P$11") (pinfunction "RF_TX/AD4/DIO4_P$11") (pintype "bidirectional"))
    )
    (net (code "95") (name "unconnected-(XB1-~{CTS}{slash}DIO7-PadP$12)") (class "Default")
      (node (ref "XB1") (pin "P$12") (pinfunction "~{CTS}/DIO7_P$12") (pintype "bidirectional"))
    )
    (net (code "96") (name "unconnected-(XB1-~{DTR}{slash}SLEEP_RQ{slash}DI8-PadP$9)") (class "Default")
      (node (ref "XB1") (pin "P$9") (pinfunction "~{DTR}/SLEEP_RQ/DI8_P$9") (pintype "bidirectional"))
    )
    (net (code "97") (name "unconnected-(XB1-~{RESET}-PadP$5)") (class "Default")
      (node (ref "XB1") (pin "P$5") (pinfunction "~{RESET}_P$5") (pintype "input"))
    )
    (net (code "98") (name "unconnected-(XB1-~{RTS}{slash}AD6{slash}DIO6-PadP$16)") (class "Default")
      (node (ref "XB1") (pin "P$16") (pinfunction "~{RTS}/AD6/DIO6_P$16") (pintype "bidirectional"))
    )
  )
)
